# PM-BAT_v0_4-35X22_86.net
KiCad netlist of a schematic drawn in EAGLE
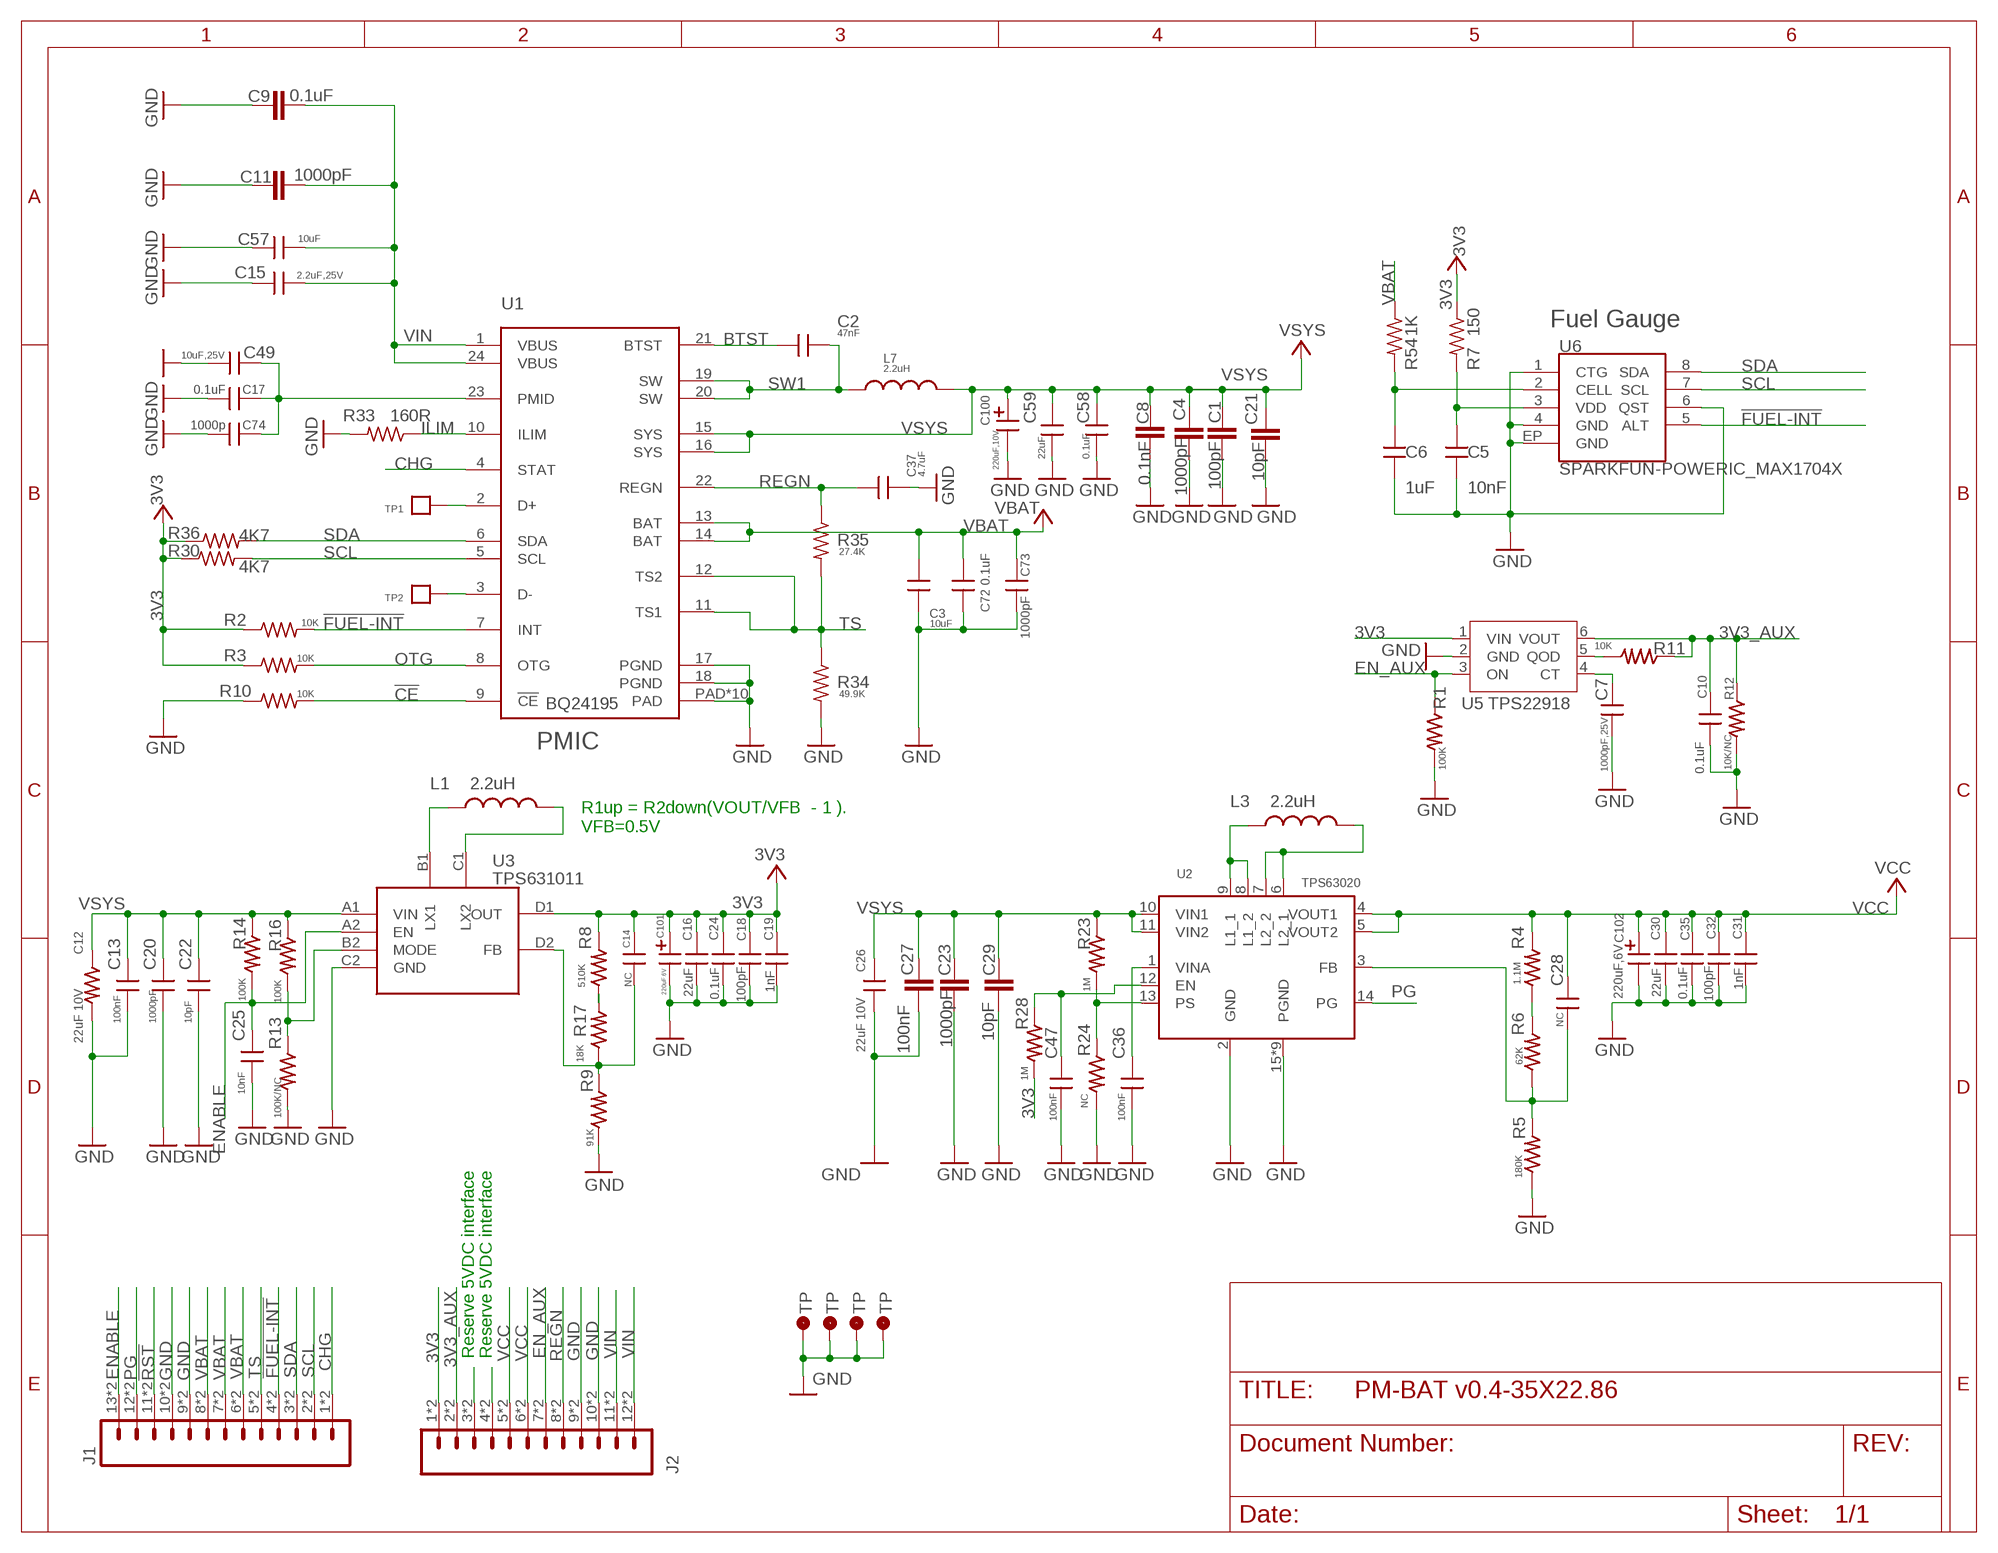
[diagram p0: schematic, sheet 1]

(export (version "E")
  (design (tool "Eeschema 10.0.6"))
  (components
    (comp (ref "C1")
      (value "100pF")
      (footprint "eagle-import:C0402_B")
      (libsource (lib "eagle-import") (part "CAP_1"))
    )
    (comp (ref "C2")
      (value "47nF")
      (footprint "eagle-import:C-0402")
      (libsource (lib "eagle-import") (part "particle SZ_CAP0402"))
    )
    (comp (ref "C3")
      (value "10uF")
      (footprint "eagle-import:C0805")
      (libsource (lib "eagle-import") (part "particle SZ_CAPC0805"))
    )
    (comp (ref "C4")
      (value "1000pF")
      (footprint "eagle-import:C0402_B")
      (libsource (lib "eagle-import") (part "CAP_1"))
    )
    (comp (ref "C5")
      (value "10nF")
      (footprint "eagle-import:C0402")
      (libsource (lib "eagle-import") (part "particle SZ_CAP0402A"))
    )
    (comp (ref "C6")
      (value "1uF")
      (footprint "eagle-import:C0402")
      (libsource (lib "eagle-import") (part "particle SZ_CAP0402A"))
    )
    (comp (ref "C7")
      (value "1000pF,25V")
      (footprint "eagle-import:C0402")
      (libsource (lib "eagle-import") (part "particle SZ_CAP0402A"))
    )
    (comp (ref "C8")
      (value "0.1nF")
      (footprint "eagle-import:C0402_B")
      (libsource (lib "eagle-import") (part "CAP_1"))
    )
    (comp (ref "C9")
      (value "0.1uF")
      (footprint "eagle-import:C0402_B")
      (libsource (lib "eagle-import") (part "CAP_1"))
    )
    (comp (ref "C10")
      (value "0.1uF")
      (footprint "eagle-import:C0201-N")
      (libsource (lib "eagle-import") (part "CAPC0201-N"))
    )
    (comp (ref "C11")
      (value "1000pF")
      (footprint "eagle-import:C0402_B")
      (libsource (lib "eagle-import") (part "CAP_1"))
    )
    (comp (ref "C12")
      (value "22uF 10V")
      (footprint "eagle-import:R-0603A")
      (libsource (lib "eagle-import") (part "RESR0603A"))
    )
    (comp (ref "C13")
      (value "100nF")
      (footprint "eagle-import:C0201-N")
      (libsource (lib "eagle-import") (part "CAPC0201-N"))
    )
    (comp (ref "C14")
      (value "NC")
      (footprint "eagle-import:C0201-N")
      (libsource (lib "eagle-import") (part "CAPC0201-N"))
    )
    (comp (ref "C15")
      (value "2.2uF,25V")
      (footprint "eagle-import:C-0603A")
      (libsource (lib "eagle-import") (part "particle SZ_CAP0603A"))
    )
    (comp (ref "C16")
      (value "22uF")
      (footprint "eagle-import:C-0603A")
      (libsource (lib "eagle-import") (part "particle SZ_21650216_CAP0603A"))
    )
    (comp (ref "C17")
      (value "0.1uF")
      (footprint "eagle-import:C0402")
      (libsource (lib "eagle-import") (part "CAP0402A"))
    )
    (comp (ref "C18")
      (value "100pF")
      (footprint "eagle-import:C0402")
      (libsource (lib "eagle-import") (part "particle SZ_CAP0402A"))
    )
    (comp (ref "C19")
      (value "1nF")
      (footprint "eagle-import:C0402")
      (libsource (lib "eagle-import") (part "particle SZ_CAP0402A"))
    )
    (comp (ref "C20")
      (value "1000pF")
      (footprint "eagle-import:C0201-N")
      (libsource (lib "eagle-import") (part "CAPC0201-N"))
    )
    (comp (ref "C21")
      (value "10pF")
      (footprint "eagle-import:C0402_B")
      (libsource (lib "eagle-import") (part "CAP_1"))
    )
    (comp (ref "C22")
      (value "10pF")
      (footprint "eagle-import:C0201-N")
      (libsource (lib "eagle-import") (part "CAPC0201-N"))
    )
    (comp (ref "C23")
      (value "1000pF")
      (footprint "eagle-import:C0402_B")
      (libsource (lib "eagle-import") (part "CAP_1"))
    )
    (comp (ref "C24")
      (value "0.1uF")
      (footprint "eagle-import:C0402")
      (libsource (lib "eagle-import") (part "particle SZ_CAP0402A"))
    )
    (comp (ref "C25")
      (value "10nF")
      (footprint "eagle-import:C0201-N")
      (libsource (lib "eagle-import") (part "CAPC0201-N"))
    )
    (comp (ref "C26")
      (value "22uF 10V")
      (footprint "eagle-import:C0603")
      (libsource (lib "eagle-import") (part "particle SZ_21650216_CAPC0603"))
    )
    (comp (ref "C27")
      (value "100nF")
      (footprint "eagle-import:C0402_B")
      (libsource (lib "eagle-import") (part "CAP_1"))
    )
    (comp (ref "C28")
      (value "NC")
      (footprint "eagle-import:C0201-N")
      (libsource (lib "eagle-import") (part "CAPC0201-N"))
    )
    (comp (ref "C29")
      (value "10pF")
      (footprint "eagle-import:C0402_B")
      (libsource (lib "eagle-import") (part "CAP_1"))
    )
    (comp (ref "C30")
      (value "22uF")
      (footprint "eagle-import:C-0603A")
      (libsource (lib "eagle-import") (part "particle SZ_21650216_CAP0603A"))
    )
    (comp (ref "C31")
      (value "1nF")
      (footprint "eagle-import:C0402")
      (libsource (lib "eagle-import") (part "particle SZ_CAP0402A"))
    )
    (comp (ref "C32")
      (value "100pF")
      (footprint "eagle-import:C0402")
      (libsource (lib "eagle-import") (part "particle SZ_CAP0402A"))
    )
    (comp (ref "C35")
      (value "0.1uF")
      (footprint "eagle-import:C0402")
      (libsource (lib "eagle-import") (part "particle SZ_CAP0402A"))
    )
    (comp (ref "C36")
      (value "100nF")
      (footprint "eagle-import:C0201-N")
      (libsource (lib "eagle-import") (part "CAPC0201-N"))
    )
    (comp (ref "C37")
      (value "4.7uF")
      (footprint "eagle-import:C0402")
      (libsource (lib "eagle-import") (part "particle SZ_CAP0402A"))
    )
    (comp (ref "C47")
      (value "100nF")
      (footprint "eagle-import:C0201-N")
      (libsource (lib "eagle-import") (part "CAPC0201-N"))
    )
    (comp (ref "C49")
      (value "10uF,25V")
      (footprint "eagle-import:C-0603A")
      (libsource (lib "eagle-import") (part "particle SZ_CAP0603A"))
    )
    (comp (ref "C57")
      (value "10uF")
      (footprint "eagle-import:C-0603A")
      (libsource (lib "eagle-import") (part "particle SZ_CAP0603A"))
    )
    (comp (ref "C58")
      (value "0.1uF")
      (footprint "eagle-import:C0402")
      (libsource (lib "eagle-import") (part "particle SZ_CAP0402A"))
    )
    (comp (ref "C59")
      (value "22uF")
      (footprint "eagle-import:C0603")
      (libsource (lib "eagle-import") (part "particle SZ_CAPC0603"))
    )
    (comp (ref "C72")
      (value "0.1uF")
      (footprint "eagle-import:C-0402")
      (libsource (lib "eagle-import") (part "particle SZ_CAP0402"))
    )
    (comp (ref "C73")
      (value "1000pF")
      (footprint "eagle-import:C-0402")
      (libsource (lib "eagle-import") (part "particle SZ_CAP0402"))
    )
    (comp (ref "C74")
      (value "1000p")
      (footprint "eagle-import:C-0402")
      (libsource (lib "eagle-import") (part "particle SZ_CAP0402"))
    )
    (comp (ref "C100")
      (value "220uF,10V")
      (footprint "eagle-import:CASE-B")
      (libsource (lib "eagle-import") (part "CAP-ECASE_B"))
    )
    (comp (ref "C101")
      (value "220uF.6V")
      (footprint "eagle-import:CASE-B")
      (libsource (lib "eagle-import") (part "CAP-ECASE_B"))
    )
    (comp (ref "C102")
      (value "220uF,6V")
      (footprint "eagle-import:CASE-B")
      (libsource (lib "eagle-import") (part "CAP-ECASE_B"))
    )
    (comp (ref "J1")
      (value "M13PTH-CST-R")
      (footprint "eagle-import:1X13-CASTELLATED")
      (libsource (lib "eagle-import") (part "M13PTH-CST-R"))
    )
    (comp (ref "J2")
      (value "M12PTH-CST-R")
      (footprint "eagle-import:1X12-CASTELLATED")
      (libsource (lib "eagle-import") (part "M12PTH-CST-R"))
    )
    (comp (ref "L1")
      (value "2.2uH")
      (footprint "eagle-import:INDUCTOR-2520")
      (libsource (lib "eagle-import") (part "INDUCTOR-SPARKFUNINDUCTOR-2520"))
    )
    (comp (ref "L3")
      (value "2.2uH")
      (footprint "eagle-import:INDUCTOR-2520")
      (libsource (lib "eagle-import") (part "INDUCTOR-SPARKFUNINDUCTOR-2520"))
    )
    (comp (ref "L7")
      (value "2.2uH")
      (footprint "eagle-import:INDUCTOR-4040")
      (libsource (lib "eagle-import") (part "INDUCTORI"))
    )
    (comp (ref "R1")
      (value "100K")
      (footprint "eagle-import:R0201-N")
      (libsource (lib "eagle-import") (part "RESR0201-N"))
    )
    (comp (ref "R2")
      (value "10K")
      (footprint "eagle-import:R0402_B")
      (libsource (lib "eagle-import") (part "Spark_R-US_"))
    )
    (comp (ref "R3")
      (value "10K")
      (footprint "eagle-import:R0402_B")
      (libsource (lib "eagle-import") (part "Spark_R-US_"))
    )
    (comp (ref "R4")
      (value "1.1M")
      (footprint "eagle-import:R0201-N")
      (libsource (lib "eagle-import") (part "RESR0201-N"))
    )
    (comp (ref "R5")
      (value "180K")
      (footprint "eagle-import:R0201-N")
      (libsource (lib "eagle-import") (part "RESR0201-N"))
    )
    (comp (ref "R6")
      (value "62K")
      (footprint "eagle-import:R0201-N")
      (libsource (lib "eagle-import") (part "RESR0201-N"))
    )
    (comp (ref "R7")
      (value "150")
      (footprint "eagle-import:R0402_B")
      (libsource (lib "eagle-import") (part "R-US_"))
    )
    (comp (ref "R8")
      (value "510K")
      (footprint "eagle-import:R0201-N")
      (libsource (lib "eagle-import") (part "RESR0201-N"))
    )
    (comp (ref "R9")
      (value "91K")
      (footprint "eagle-import:R0201-N")
      (libsource (lib "eagle-import") (part "RESR0201-N"))
    )
    (comp (ref "R10")
      (value "10K")
      (footprint "eagle-import:R0402_B")
      (libsource (lib "eagle-import") (part "Spark_R-US_"))
    )
    (comp (ref "R11")
      (value "10K")
      (footprint "eagle-import:R0201-N")
      (libsource (lib "eagle-import") (part "RESR0201-N"))
    )
    (comp (ref "R12")
      (value "10K/NC")
      (footprint "eagle-import:R0201-N")
      (libsource (lib "eagle-import") (part "RESR0201-N"))
    )
    (comp (ref "R13")
      (value "100K/NC")
      (footprint "eagle-import:R0201-N")
      (libsource (lib "eagle-import") (part "RESR0201-N"))
    )
    (comp (ref "R14")
      (value "100K")
      (footprint "eagle-import:R0201-N")
      (libsource (lib "eagle-import") (part "RESR0201-N"))
    )
    (comp (ref "R16")
      (value "100K")
      (footprint "eagle-import:R0201-N")
      (libsource (lib "eagle-import") (part "RESR0201-N"))
    )
    (comp (ref "R17")
      (value "18K")
      (footprint "eagle-import:R0201-N")
      (libsource (lib "eagle-import") (part "RESR0201-N"))
    )
    (comp (ref "R23")
      (value "1M")
      (footprint "eagle-import:R0201-N")
      (libsource (lib "eagle-import") (part "RESR0201-N"))
    )
    (comp (ref "R24")
      (value "NC")
      (footprint "eagle-import:R0201-N")
      (libsource (lib "eagle-import") (part "RESR0201-N"))
    )
    (comp (ref "R28")
      (value "1M")
      (footprint "eagle-import:R0201-N")
      (libsource (lib "eagle-import") (part "RESR0201-N"))
    )
    (comp (ref "R30")
      (value "4K7")
      (footprint "eagle-import:R0402_B")
      (libsource (lib "eagle-import") (part "R-US_"))
    )
    (comp (ref "R33")
      (value "160R")
      (footprint "eagle-import:R0402_B")
      (libsource (lib "eagle-import") (part "R-US_"))
    )
    (comp (ref "R34")
      (value "49.9K")
      (footprint "eagle-import:R0402_B")
      (libsource (lib "eagle-import") (part "Spark_R-US_"))
    )
    (comp (ref "R35")
      (value "27.4K")
      (footprint "eagle-import:R0402_B")
      (libsource (lib "eagle-import") (part "Spark_R-US_"))
    )
    (comp (ref "R36")
      (value "4K7")
      (footprint "eagle-import:R0402_B")
      (libsource (lib "eagle-import") (part "R-US_"))
    )
    (comp (ref "R54")
      (value "1K")
      (footprint "eagle-import:R0402_B")
      (libsource (lib "eagle-import") (part "R-US_"))
    )
    (comp (ref "TP1")
      (value "TP1311MM")
      (footprint "eagle-import:TP-1311MM")
      (libsource (lib "eagle-import") (part "TP1311MM"))
    )
    (comp (ref "TP2")
      (value "TP1311MM")
      (footprint "eagle-import:TP-1311MM")
      (libsource (lib "eagle-import") (part "TP1311MM"))
    )
    (comp (ref "U$1")
      (value "TP")
      (footprint "eagle-import:TP_2.33X1.37")
      (libsource (lib "eagle-import") (part "TP"))
    )
    (comp (ref "U$2")
      (value "TP")
      (footprint "eagle-import:TP_2.33X1.37")
      (libsource (lib "eagle-import") (part "TP"))
    )
    (comp (ref "U$4")
      (value "TP")
      (footprint "eagle-import:TP_2.33X1.37")
      (libsource (lib "eagle-import") (part "TP"))
    )
    (comp (ref "U$5")
      (value "TP")
      (footprint "eagle-import:TP_2.33X1.37")
      (libsource (lib "eagle-import") (part "TP"))
    )
    (comp (ref "U1")
      (value "BQ24195")
      (footprint "eagle-import:ELECTRON_QFN24")
      (libsource (lib "eagle-import") (part "ELECTRON_BQ24298RTWR"))
    )
    (comp (ref "U2")
      (value "TPS63020")
      (footprint "eagle-import:TPS63020")
      (libsource (lib "eagle-import") (part "TPS63020"))
    )
    (comp (ref "U3")
      (value "TPS631011")
      (footprint "eagle-import:DSBGA")
      (libsource (lib "eagle-import") (part "TPS631010"))
    )
    (comp (ref "U5")
      (value "TPS22918")
      (footprint "eagle-import:SOT-23-6")
      (libsource (lib "eagle-import") (part "TPS22918"))
    )
    (comp (ref "U6")
      (value "SPARKFUN-POWERIC_MAX1704X")
      (footprint "eagle-import:SPARKFUN-POWERIC_TDFN-8")
      (libsource (lib "eagle-import") (part "SPARKFUN-POWERIC_MAX1704X"))
    )
  )
  (nets
    (net (code "1") (name "/3V3_AUX") (class "Default")
      (node (ref "C10") (pin "1") (pinfunction "1_1") (pintype "bidirectional"))
      (node (ref "J2") (pin "2") (pinfunction "2_2") (pintype "passive"))
      (node (ref "J2") (pin "@2") (pinfunction "2_@2") (pintype "passive"))
      (node (ref "R11") (pin "1") (pinfunction "1_1") (pintype "bidirectional"))
      (node (ref "R12") (pin "1") (pinfunction "1_1") (pintype "bidirectional"))
      (node (ref "U5") (pin "6") (pinfunction "VOUT_6") (pintype "bidirectional"))
    )
    (net (code "2") (name "/BTST") (class "Default")
      (node (ref "C2") (pin "1") (pinfunction "1_1") (pintype "bidirectional"))
      (node (ref "U1") (pin "21") (pinfunction "BTST_21") (pintype "bidirectional"))
    )
    (net (code "3") (name "/CHG") (class "Default")
      (node (ref "J1") (pin "1") (pinfunction "1_1") (pintype "passive"))
      (node (ref "J1") (pin "@1") (pinfunction "1_@1") (pintype "passive"))
      (node (ref "U1") (pin "4") (pinfunction "STAT_4") (pintype "bidirectional"))
    )
    (net (code "4") (name "/ENABLE") (class "Default")
      (node (ref "C25") (pin "1") (pinfunction "1_1") (pintype "bidirectional"))
      (node (ref "J1") (pin "13") (pinfunction "13_13") (pintype "passive"))
      (node (ref "J1") (pin "@13") (pinfunction "13_@13") (pintype "passive"))
      (node (ref "R14") (pin "2") (pinfunction "2_2") (pintype "bidirectional"))
      (node (ref "U3") (pin "A2") (pinfunction "EN_A2") (pintype "bidirectional"))
    )
    (net (code "5") (name "/EN_AUX") (class "Default")
      (node (ref "J2") (pin "7") (pinfunction "7_7") (pintype "passive"))
      (node (ref "J2") (pin "@7") (pinfunction "7_@7") (pintype "passive"))
      (node (ref "R1") (pin "1") (pinfunction "1_1") (pintype "bidirectional"))
      (node (ref "U5") (pin "3") (pinfunction "ON_3") (pintype "bidirectional"))
    )
    (net (code "6") (name "/ILIM") (class "Default")
      (node (ref "R33") (pin "1") (pinfunction "1_1") (pintype "passive"))
      (node (ref "U1") (pin "10") (pinfunction "ILIM_10") (pintype "output"))
    )
    (net (code "7") (name "/OTG") (class "Default")
      (node (ref "R3") (pin "2") (pinfunction "2_2") (pintype "passive"))
      (node (ref "U1") (pin "8") (pinfunction "OTG_8") (pintype "bidirectional"))
    )
    (net (code "8") (name "/PG") (class "Default")
      (node (ref "J1") (pin "12") (pinfunction "12_12") (pintype "passive"))
      (node (ref "J1") (pin "@12") (pinfunction "12_@12") (pintype "passive"))
      (node (ref "U2") (pin "14") (pinfunction "PG_14") (pintype "bidirectional"))
    )
    (net (code "9") (name "/REGN") (class "Default")
      (node (ref "C37") (pin "1") (pinfunction "1_1") (pintype "bidirectional"))
      (node (ref "J2") (pin "8") (pinfunction "8_8") (pintype "passive"))
      (node (ref "J2") (pin "@8") (pinfunction "8_@8") (pintype "passive"))
      (node (ref "R35") (pin "1") (pinfunction "1_1") (pintype "passive"))
      (node (ref "U1") (pin "22") (pinfunction "REGN_22") (pintype "bidirectional"))
    )
    (net (code "10") (name "/SCL") (class "Default")
      (node (ref "J1") (pin "2") (pinfunction "2_2") (pintype "passive"))
      (node (ref "J1") (pin "@2") (pinfunction "2_@2") (pintype "passive"))
      (node (ref "R30") (pin "2") (pinfunction "2_2") (pintype "passive"))
      (node (ref "U1") (pin "5") (pinfunction "SCL_5") (pintype "output"))
      (node (ref "U6") (pin "7") (pinfunction "SCL_7") (pintype "bidirectional"))
    )
    (net (code "11") (name "/SDA") (class "Default")
      (node (ref "J1") (pin "3") (pinfunction "3_3") (pintype "passive"))
      (node (ref "J1") (pin "@3") (pinfunction "3_@3") (pintype "passive"))
      (node (ref "R36") (pin "2") (pinfunction "2_2") (pintype "passive"))
      (node (ref "U1") (pin "6") (pinfunction "SDA_6") (pintype "bidirectional"))
      (node (ref "U6") (pin "8") (pinfunction "SDA_8") (pintype "bidirectional"))
    )
    (net (code "12") (name "/SW1") (class "Default")
      (node (ref "C2") (pin "2") (pinfunction "2_2") (pintype "bidirectional"))
      (node (ref "L7") (pin "P$1") (pinfunction "1_P$1") (pintype "passive"))
      (node (ref "U1") (pin "19") (pinfunction "SW_19") (pintype "power_in"))
      (node (ref "U1") (pin "20") (pinfunction "SW_20") (pintype "power_in"))
    )
    (net (code "13") (name "/TS") (class "Default")
      (node (ref "J1") (pin "5") (pinfunction "5_5") (pintype "passive"))
      (node (ref "J1") (pin "@5") (pinfunction "5_@5") (pintype "passive"))
      (node (ref "R34") (pin "1") (pinfunction "1_1") (pintype "passive"))
      (node (ref "R35") (pin "2") (pinfunction "2_2") (pintype "passive"))
      (node (ref "U1") (pin "11") (pinfunction "TS1_11") (pintype "bidirectional"))
      (node (ref "U1") (pin "12") (pinfunction "TS2_12") (pintype "bidirectional"))
    )
    (net (code "14") (name "/VIN") (class "Default")
      (node (ref "C11") (pin "2") (pinfunction "P$2_2") (pintype "passive"))
      (node (ref "C15") (pin "1") (pinfunction "1_1") (pintype "bidirectional"))
      (node (ref "C57") (pin "1") (pinfunction "1_1") (pintype "bidirectional"))
      (node (ref "C9") (pin "2") (pinfunction "P$2_2") (pintype "passive"))
      (node (ref "J2") (pin "11") (pinfunction "11_11") (pintype "passive"))
      (node (ref "J2") (pin "12") (pinfunction "12_12") (pintype "passive"))
      (node (ref "J2") (pin "@11") (pinfunction "11_@11") (pintype "passive"))
      (node (ref "J2") (pin "@12") (pinfunction "12_@12") (pintype "passive"))
      (node (ref "U1") (pin "1") (pinfunction "VBUS_1") (pintype "power_in"))
      (node (ref "U1") (pin "24") (pinfunction "VBUS_24") (pintype "passive"))
    )
    (net (code "15") (name "/~{CE}") (class "Default")
      (node (ref "R10") (pin "2") (pinfunction "2_2") (pintype "passive"))
      (node (ref "U1") (pin "9") (pinfunction "~{CE}_9") (pintype "output"))
    )
    (net (code "16") (name "/~{FUEL-INT}") (class "Default")
      (node (ref "J1") (pin "4") (pinfunction "4_4") (pintype "passive"))
      (node (ref "J1") (pin "@4") (pinfunction "4_@4") (pintype "passive"))
      (node (ref "R2") (pin "2") (pinfunction "2_2") (pintype "passive"))
      (node (ref "U1") (pin "7") (pinfunction "INT_7") (pintype "bidirectional"))
      (node (ref "U6") (pin "5") (pinfunction "ALT_5") (pintype "bidirectional"))
    )
    (net (code "17") (name "/~{RST}") (class "Default")
      (node (ref "J1") (pin "11") (pinfunction "11_11") (pintype "passive"))
      (node (ref "J1") (pin "@11") (pinfunction "11_@11") (pintype "passive"))
    )
    (net (code "18") (name "3V3") (class "Default")
      (node (ref "C101") (pin "P$1") (pinfunction "1_P$1") (pintype "bidirectional"))
      (node (ref "C14") (pin "1") (pinfunction "1_1") (pintype "bidirectional"))
      (node (ref "C16") (pin "1") (pinfunction "1_1") (pintype "bidirectional"))
      (node (ref "C18") (pin "1") (pinfunction "1_1") (pintype "bidirectional"))
      (node (ref "C19") (pin "1") (pinfunction "1_1") (pintype "bidirectional"))
      (node (ref "C24") (pin "1") (pinfunction "1_1") (pintype "bidirectional"))
      (node (ref "J2") (pin "1") (pinfunction "1_1") (pintype "passive"))
      (node (ref "J2") (pin "@1") (pinfunction "1_@1") (pintype "passive"))
      (node (ref "R2") (pin "1") (pinfunction "1_1") (pintype "passive"))
      (node (ref "R28") (pin "2") (pinfunction "2_2") (pintype "bidirectional"))
      (node (ref "R3") (pin "1") (pinfunction "1_1") (pintype "passive"))
      (node (ref "R30") (pin "1") (pinfunction "1_1") (pintype "passive"))
      (node (ref "R36") (pin "1") (pinfunction "1_1") (pintype "passive"))
      (node (ref "R7") (pin "1") (pinfunction "1_1") (pintype "passive"))
      (node (ref "R8") (pin "2") (pinfunction "2_2") (pintype "bidirectional"))
      (node (ref "U3") (pin "D1") (pinfunction "OUT_D1") (pintype "bidirectional"))
      (node (ref "U5") (pin "1") (pinfunction "VIN_1") (pintype "bidirectional"))
    )
    (net (code "19") (name "GND") (class "Default")
      (node (ref "C1") (pin "1") (pinfunction "P$1_1") (pintype "passive"))
      (node (ref "C10") (pin "2") (pinfunction "2_2") (pintype "bidirectional"))
      (node (ref "C100") (pin "P$2") (pinfunction "2_P$2") (pintype "bidirectional"))
      (node (ref "C101") (pin "P$2") (pinfunction "2_P$2") (pintype "bidirectional"))
      (node (ref "C102") (pin "P$2") (pinfunction "2_P$2") (pintype "bidirectional"))
      (node (ref "C11") (pin "1") (pinfunction "P$1_1") (pintype "passive"))
      (node (ref "C12") (pin "2") (pinfunction "2_2") (pintype "bidirectional"))
      (node (ref "C13") (pin "2") (pinfunction "2_2") (pintype "bidirectional"))
      (node (ref "C15") (pin "2") (pinfunction "2_2") (pintype "bidirectional"))
      (node (ref "C16") (pin "2") (pinfunction "2_2") (pintype "bidirectional"))
      (node (ref "C17") (pin "1") (pinfunction "1_1") (pintype "bidirectional"))
      (node (ref "C18") (pin "2") (pinfunction "2_2") (pintype "bidirectional"))
      (node (ref "C19") (pin "2") (pinfunction "2_2") (pintype "bidirectional"))
      (node (ref "C20") (pin "2") (pinfunction "2_2") (pintype "bidirectional"))
      (node (ref "C21") (pin "1") (pinfunction "P$1_1") (pintype "passive"))
      (node (ref "C22") (pin "2") (pinfunction "2_2") (pintype "bidirectional"))
      (node (ref "C23") (pin "1") (pinfunction "P$1_1") (pintype "passive"))
      (node (ref "C24") (pin "2") (pinfunction "2_2") (pintype "bidirectional"))
      (node (ref "C25") (pin "2") (pinfunction "2_2") (pintype "bidirectional"))
      (node (ref "C26") (pin "2") (pinfunction "2_2") (pintype "bidirectional"))
      (node (ref "C27") (pin "1") (pinfunction "P$1_1") (pintype "passive"))
      (node (ref "C29") (pin "1") (pinfunction "P$1_1") (pintype "passive"))
      (node (ref "C3") (pin "2") (pinfunction "2_2") (pintype "bidirectional"))
      (node (ref "C30") (pin "2") (pinfunction "2_2") (pintype "bidirectional"))
      (node (ref "C31") (pin "2") (pinfunction "2_2") (pintype "bidirectional"))
      (node (ref "C32") (pin "2") (pinfunction "2_2") (pintype "bidirectional"))
      (node (ref "C35") (pin "2") (pinfunction "2_2") (pintype "bidirectional"))
      (node (ref "C36") (pin "2") (pinfunction "2_2") (pintype "bidirectional"))
      (node (ref "C37") (pin "2") (pinfunction "2_2") (pintype "bidirectional"))
      (node (ref "C4") (pin "1") (pinfunction "P$1_1") (pintype "passive"))
      (node (ref "C47") (pin "2") (pinfunction "2_2") (pintype "bidirectional"))
      (node (ref "C49") (pin "2") (pinfunction "2_2") (pintype "bidirectional"))
      (node (ref "C5") (pin "2") (pinfunction "2_2") (pintype "bidirectional"))
      (node (ref "C57") (pin "2") (pinfunction "2_2") (pintype "bidirectional"))
      (node (ref "C58") (pin "2") (pinfunction "2_2") (pintype "bidirectional"))
      (node (ref "C59") (pin "2") (pinfunction "2_2") (pintype "bidirectional"))
      (node (ref "C6") (pin "2") (pinfunction "2_2") (pintype "bidirectional"))
      (node (ref "C7") (pin "2") (pinfunction "2_2") (pintype "bidirectional"))
      (node (ref "C72") (pin "2") (pinfunction "2_2") (pintype "bidirectional"))
      (node (ref "C73") (pin "2") (pinfunction "2_2") (pintype "bidirectional"))
      (node (ref "C74") (pin "1") (pinfunction "1_1") (pintype "bidirectional"))
      (node (ref "C8") (pin "1") (pinfunction "P$1_1") (pintype "passive"))
      (node (ref "C9") (pin "1") (pinfunction "P$1_1") (pintype "passive"))
      (node (ref "J1") (pin "10") (pinfunction "10_10") (pintype "passive"))
      (node (ref "J1") (pin "9") (pinfunction "9_9") (pintype "passive"))
      (node (ref "J1") (pin "@10") (pinfunction "10_@10") (pintype "passive"))
      (node (ref "J1") (pin "@9") (pinfunction "9_@9") (pintype "passive"))
      (node (ref "J2") (pin "10") (pinfunction "10_10") (pintype "passive"))
      (node (ref "J2") (pin "9") (pinfunction "9_9") (pintype "passive"))
      (node (ref "J2") (pin "@10") (pinfunction "10_@10") (pintype "passive"))
      (node (ref "J2") (pin "@9") (pinfunction "9_@9") (pintype "passive"))
      (node (ref "R1") (pin "2") (pinfunction "2_2") (pintype "bidirectional"))
      (node (ref "R10") (pin "1") (pinfunction "1_1") (pintype "passive"))
      (node (ref "R12") (pin "2") (pinfunction "2_2") (pintype "bidirectional"))
      (node (ref "R13") (pin "2") (pinfunction "2_2") (pintype "bidirectional"))
      (node (ref "R24") (pin "2") (pinfunction "2_2") (pintype "bidirectional"))
      (node (ref "R33") (pin "2") (pinfunction "2_2") (pintype "passive"))
      (node (ref "R34") (pin "2") (pinfunction "2_2") (pintype "passive"))
      (node (ref "R5") (pin "1") (pinfunction "1_1") (pintype "bidirectional"))
      (node (ref "R9") (pin "1") (pinfunction "1_1") (pintype "bidirectional"))
      (node (ref "U$1") (pin "1") (pinfunction "TP_1") (pintype "bidirectional"))
      (node (ref "U$2") (pin "1") (pinfunction "TP_1") (pintype "bidirectional"))
      (node (ref "U$4") (pin "1") (pinfunction "TP_1") (pintype "bidirectional"))
      (node (ref "U$5") (pin "1") (pinfunction "TP_1") (pintype "bidirectional"))
      (node (ref "U1") (pin "17") (pinfunction "PGND_17") (pintype "passive"))
      (node (ref "U1") (pin "18") (pinfunction "PGND_18") (pintype "passive"))
      (node (ref "U1") (pin "PAD") (pinfunction "PAD_PAD") (pintype "power_in"))
      (node (ref "U1") (pin "PAD@1") (pinfunction "PAD_PAD@1") (pintype "power_in"))
      (node (ref "U1") (pin "PAD@2") (pinfunction "PAD_PAD@2") (pintype "power_in"))
      (node (ref "U1") (pin "PAD@3") (pinfunction "PAD_PAD@3") (pintype "power_in"))
      (node (ref "U1") (pin "PAD@4") (pinfunction "PAD_PAD@4") (pintype "power_in"))
      (node (ref "U1") (pin "PAD@5") (pinfunction "PAD_PAD@5") (pintype "power_in"))
      (node (ref "U1") (pin "PAD@6") (pinfunction "PAD_PAD@6") (pintype "power_in"))
      (node (ref "U1") (pin "PAD@7") (pinfunction "PAD_PAD@7") (pintype "power_in"))
      (node (ref "U1") (pin "PAD@8") (pinfunction "PAD_PAD@8") (pintype "power_in"))
      (node (ref "U1") (pin "PAD@9") (pinfunction "PAD_PAD@9") (pintype "power_in"))
      (node (ref "U2") (pin "15") (pinfunction "PGND_15") (pintype "bidirectional"))
      (node (ref "U2") (pin "16") (pinfunction "PGND_16") (pintype "bidirectional"))
      (node (ref "U2") (pin "17") (pinfunction "PGND_17") (pintype "bidirectional"))
      (node (ref "U2") (pin "18") (pinfunction "PGND_18") (pintype "bidirectional"))
      (node (ref "U2") (pin "19") (pinfunction "PGND_19") (pintype "bidirectional"))
      (node (ref "U2") (pin "2") (pinfunction "GND_2") (pintype "bidirectional"))
      (node (ref "U2") (pin "20") (pinfunction "PGND_20") (pintype "bidirectional"))
      (node (ref "U2") (pin "21") (pinfunction "PGND_21") (pintype "bidirectional"))
      (node (ref "U2") (pin "22") (pinfunction "PGND_22") (pintype "bidirectional"))
      (node (ref "U2") (pin "23") (pinfunction "PGND_23") (pintype "bidirectional"))
      (node (ref "U3") (pin "C2") (pinfunction "GND_C2") (pintype "bidirectional"))
      (node (ref "U5") (pin "2") (pinfunction "GND_2") (pintype "bidirectional"))
      (node (ref "U6") (pin "1") (pinfunction "CTG_1") (pintype "bidirectional"))
      (node (ref "U6") (pin "4") (pinfunction "GND_4") (pintype "bidirectional"))
      (node (ref "U6") (pin "6") (pinfunction "QST_6") (pintype "bidirectional"))
      (node (ref "U6") (pin "EP") (pinfunction "GND_EP") (pintype "bidirectional"))
    )
    (net (code "20") (name "Net-(J2-3-Pad@3)") (class "Default")
      (node (ref "J2") (pin "3") (pinfunction "3_3") (pintype "passive"))
      (node (ref "J2") (pin "@3") (pinfunction "3_@3") (pintype "passive"))
    )
    (net (code "21") (name "Net-(J2-4-Pad@4)") (class "Default")
      (node (ref "J2") (pin "4") (pinfunction "4_4") (pintype "passive"))
      (node (ref "J2") (pin "@4") (pinfunction "4_@4") (pintype "passive"))
    )
    (net (code "22") (name "Net-(R4-Pad1)") (class "Default")
      (node (ref "R4") (pin "1") (pinfunction "1_1") (pintype "bidirectional"))
      (node (ref "R6") (pin "2") (pinfunction "2_2") (pintype "bidirectional"))
    )
    (net (code "23") (name "Net-(R17-Pad2)") (class "Default")
      (node (ref "R17") (pin "2") (pinfunction "2_2") (pintype "bidirectional"))
      (node (ref "R8") (pin "1") (pinfunction "1_1") (pintype "bidirectional"))
    )
    (net (code "24") (name "Net-(TP1-1)") (class "Default")
      (node (ref "TP1") (pin "P$1") (pinfunction "1_P$1") (pintype "bidirectional"))
      (node (ref "U1") (pin "2") (pinfunction "D+_2") (pintype "output"))
    )
    (net (code "25") (name "Net-(TP2-1)") (class "Default")
      (node (ref "TP2") (pin "P$1") (pinfunction "1_P$1") (pintype "bidirectional"))
      (node (ref "U1") (pin "3") (pinfunction "D-_3") (pintype "output"))
    )
    (net (code "26") (name "Net-(U1-PMID)") (class "Default")
      (node (ref "C17") (pin "2") (pinfunction "2_2") (pintype "bidirectional"))
      (node (ref "C49") (pin "1") (pinfunction "1_1") (pintype "bidirectional"))
      (node (ref "C74") (pin "2") (pinfunction "2_2") (pintype "bidirectional"))
      (node (ref "U1") (pin "23") (pinfunction "PMID_23") (pintype "passive"))
    )
    (net (code "27") (name "Net-(U2-EN)") (class "Default")
      (node (ref "C47") (pin "1") (pinfunction "1_1") (pintype "bidirectional"))
      (node (ref "R28") (pin "1") (pinfunction "1_1") (pintype "bidirectional"))
      (node (ref "U2") (pin "12") (pinfunction "EN_12") (pintype "bidirectional"))
    )
    (net (code "28") (name "Net-(U2-FB)") (class "Default")
      (node (ref "C28") (pin "2") (pinfunction "2_2") (pintype "bidirectional"))
      (node (ref "R5") (pin "2") (pinfunction "2_2") (pintype "bidirectional"))
      (node (ref "R6") (pin "1") (pinfunction "1_1") (pintype "bidirectional"))
      (node (ref "U2") (pin "3") (pinfunction "FB_3") (pintype "bidirectional"))
    )
    (net (code "29") (name "Net-(U2-L1_1)") (class "Default")
      (node (ref "L3") (pin "1") (pinfunction "1_1") (pintype "passive"))
      (node (ref "U2") (pin "8") (pinfunction "L1_2_8") (pintype "bidirectional"))
      (node (ref "U2") (pin "9") (pinfunction "L1_1_9") (pintype "bidirectional"))
    )
    (net (code "30") (name "Net-(U2-L2_1)") (class "Default")
      (node (ref "L3") (pin "2") (pinfunction "2_2") (pintype "passive"))
      (node (ref "U2") (pin "6") (pinfunction "L2_1_6") (pintype "bidirectional"))
      (node (ref "U2") (pin "7") (pinfunction "L2_2_7") (pintype "bidirectional"))
    )
    (net (code "31") (name "Net-(U2-PS)") (class "Default")
      (node (ref "R23") (pin "2") (pinfunction "2_2") (pintype "bidirectional"))
      (node (ref "R24") (pin "1") (pinfunction "1_1") (pintype "bidirectional"))
      (node (ref "U2") (pin "13") (pinfunction "PS_13") (pintype "bidirectional"))
    )
    (net (code "32") (name "Net-(U2-VINA)") (class "Default")
      (node (ref "C36") (pin "1") (pinfunction "1_1") (pintype "bidirectional"))
      (node (ref "U2") (pin "1") (pinfunction "VINA_1") (pintype "bidirectional"))
    )
    (net (code "33") (name "Net-(U3-FB)") (class "Default")
      (node (ref "C14") (pin "2") (pinfunction "2_2") (pintype "bidirectional"))
      (node (ref "R17") (pin "1") (pinfunction "1_1") (pintype "bidirectional"))
      (node (ref "R9") (pin "2") (pinfunction "2_2") (pintype "bidirectional"))
      (node (ref "U3") (pin "D2") (pinfunction "FB_D2") (pintype "bidirectional"))
    )
    (net (code "34") (name "Net-(U3-LX1)") (class "Default")
      (node (ref "L1") (pin "1") (pinfunction "1_1") (pintype "passive"))
      (node (ref "U3") (pin "B1") (pinfunction "LX1_B1") (pintype "bidirectional"))
    )
    (net (code "35") (name "Net-(U3-LX2)") (class "Default")
      (node (ref "L1") (pin "2") (pinfunction "2_2") (pintype "passive"))
      (node (ref "U3") (pin "C1") (pinfunction "LX2_C1") (pintype "bidirectional"))
    )
    (net (code "36") (name "Net-(U3-MODE)") (class "Default")
      (node (ref "R13") (pin "1") (pinfunction "1_1") (pintype "bidirectional"))
      (node (ref "R16") (pin "2") (pinfunction "2_2") (pintype "bidirectional"))
      (node (ref "U3") (pin "B2") (pinfunction "MODE_B2") (pintype "bidirectional"))
    )
    (net (code "37") (name "Net-(U5-CT)") (class "Default")
      (node (ref "C7") (pin "1") (pinfunction "1_1") (pintype "bidirectional"))
      (node (ref "U5") (pin "4") (pinfunction "CT_4") (pintype "bidirectional"))
    )
    (net (code "38") (name "Net-(U5-QOD)") (class "Default")
      (node (ref "R11") (pin "2") (pinfunction "2_2") (pintype "bidirectional"))
      (node (ref "U5") (pin "5") (pinfunction "QOD_5") (pintype "bidirectional"))
    )
    (net (code "39") (name "Net-(U6-CELL)") (class "Default")
      (node (ref "C6") (pin "1") (pinfunction "1_1") (pintype "bidirectional"))
      (node (ref "R54") (pin "2") (pinfunction "2_2") (pintype "passive"))
      (node (ref "U6") (pin "2") (pinfunction "CELL_2") (pintype "bidirectional"))
    )
    (net (code "40") (name "Net-(U6-VDD)") (class "Default")
      (node (ref "C5") (pin "1") (pinfunction "1_1") (pintype "bidirectional"))
      (node (ref "R7") (pin "2") (pinfunction "2_2") (pintype "passive"))
      (node (ref "U6") (pin "3") (pinfunction "VDD_3") (pintype "bidirectional"))
    )
    (net (code "41") (name "VBAT") (class "Default")
      (node (ref "C3") (pin "1") (pinfunction "1_1") (pintype "bidirectional"))
      (node (ref "C72") (pin "1") (pinfunction "1_1") (pintype "bidirectional"))
      (node (ref "C73") (pin "1") (pinfunction "1_1") (pintype "bidirectional"))
      (node (ref "J1") (pin "6") (pinfunction "6_6") (pintype "passive"))
      (node (ref "J1") (pin "7") (pinfunction "7_7") (pintype "passive"))
      (node (ref "J1") (pin "8") (pinfunction "8_8") (pintype "passive"))
      (node (ref "J1") (pin "@6") (pinfunction "6_@6") (pintype "passive"))
      (node (ref "J1") (pin "@7") (pinfunction "7_@7") (pintype "passive"))
      (node (ref "J1") (pin "@8") (pinfunction "8_@8") (pintype "passive"))
      (node (ref "R54") (pin "1") (pinfunction "1_1") (pintype "passive"))
      (node (ref "U1") (pin "13") (pinfunction "BAT_13") (pintype "passive"))
      (node (ref "U1") (pin "14") (pinfunction "BAT_14") (pintype "power_in"))
    )
    (net (code "42") (name "VCC") (class "Default")
      (node (ref "C102") (pin "P$1") (pinfunction "1_P$1") (pintype "bidirectional"))
      (node (ref "C28") (pin "1") (pinfunction "1_1") (pintype "bidirectional"))
      (node (ref "C30") (pin "1") (pinfunction "1_1") (pintype "bidirectional"))
      (node (ref "C31") (pin "1") (pinfunction "1_1") (pintype "bidirectional"))
      (node (ref "C32") (pin "1") (pinfunction "1_1") (pintype "bidirectional"))
      (node (ref "C35") (pin "1") (pinfunction "1_1") (pintype "bidirectional"))
      (node (ref "J2") (pin "5") (pinfunction "5_5") (pintype "passive"))
      (node (ref "J2") (pin "6") (pinfunction "6_6") (pintype "passive"))
      (node (ref "J2") (pin "@5") (pinfunction "5_@5") (pintype "passive"))
      (node (ref "J2") (pin "@6") (pinfunction "6_@6") (pintype "passive"))
      (node (ref "R4") (pin "2") (pinfunction "2_2") (pintype "bidirectional"))
      (node (ref "U2") (pin "4") (pinfunction "VOUT1_4") (pintype "bidirectional"))
      (node (ref "U2") (pin "5") (pinfunction "VOUT2_5") (pintype "bidirectional"))
    )
    (net (code "43") (name "VSYS") (class "Default")
      (node (ref "C1") (pin "2") (pinfunction "P$2_2") (pintype "passive"))
      (node (ref "C100") (pin "P$1") (pinfunction "1_P$1") (pintype "bidirectional"))
      (node (ref "C12") (pin "1") (pinfunction "1_1") (pintype "bidirectional"))
      (node (ref "C13") (pin "1") (pinfunction "1_1") (pintype "bidirectional"))
      (node (ref "C20") (pin "1") (pinfunction "1_1") (pintype "bidirectional"))
      (node (ref "C21") (pin "2") (pinfunction "P$2_2") (pintype "passive"))
      (node (ref "C22") (pin "1") (pinfunction "1_1") (pintype "bidirectional"))
      (node (ref "C23") (pin "2") (pinfunction "P$2_2") (pintype "passive"))
      (node (ref "C26") (pin "1") (pinfunction "1_1") (pintype "bidirectional"))
      (node (ref "C27") (pin "2") (pinfunction "P$2_2") (pintype "passive"))
      (node (ref "C29") (pin "2") (pinfunction "P$2_2") (pintype "passive"))
      (node (ref "C4") (pin "2") (pinfunction "P$2_2") (pintype "passive"))
      (node (ref "C58") (pin "1") (pinfunction "1_1") (pintype "bidirectional"))
      (node (ref "C59") (pin "1") (pinfunction "1_1") (pintype "bidirectional"))
      (node (ref "C8") (pin "2") (pinfunction "P$2_2") (pintype "passive"))
      (node (ref "L7") (pin "P$2") (pinfunction "2_P$2") (pintype "passive"))
      (node (ref "R14") (pin "1") (pinfunction "1_1") (pintype "bidirectional"))
      (node (ref "R16") (pin "1") (pinfunction "1_1") (pintype "bidirectional"))
      (node (ref "R23") (pin "1") (pinfunction "1_1") (pintype "bidirectional"))
      (node (ref "U1") (pin "15") (pinfunction "SYS_15") (pintype "power_in"))
      (node (ref "U1") (pin "16") (pinfunction "SYS_16") (pintype "power_in"))
      (node (ref "U2") (pin "10") (pinfunction "VIN1_10") (pintype "bidirectional"))
      (node (ref "U2") (pin "11") (pinfunction "VIN2_11") (pintype "bidirectional"))
      (node (ref "U3") (pin "A1") (pinfunction "VIN_A1") (pintype "bidirectional"))
    )
  )
)
